# Connectors.net
KiCad netlist of a schematic drawn in Altium Designer
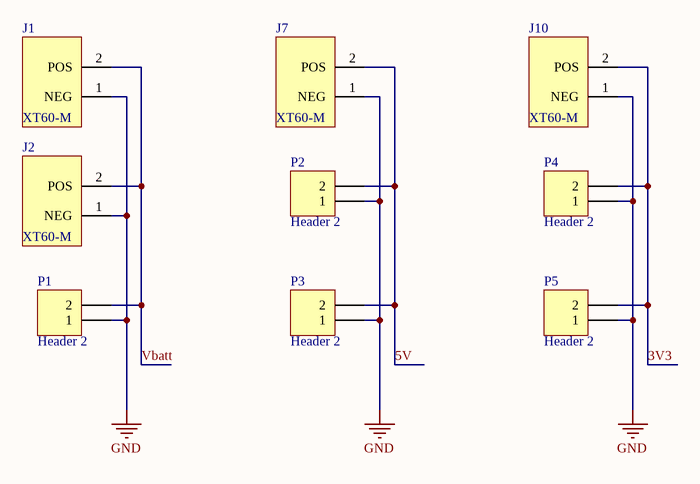
[diagram p0: Connectors.SchDoc]

(export (version "E")
  (design (tool "Eeschema 10.0.6"))
  (components
    (comp (ref "J1")
      (value "XT60-M")
      (footprint "*AMASS_XT60-M")
      (description "Plug; DC supply; XT60; male; PIN: 2; for cable; soldered; 30A; 500V")
      (fields (field (name "MF") "AMASS"))
      (libsource (lib "XT60-M") (part "XT60-M"))
    )
    (comp (ref "J2")
      (value "XT60-M")
      (footprint "*AMASS_XT60-M")
      (description "Plug; DC supply; XT60; male; PIN: 2; for cable; soldered; 30A; 500V")
      (fields (field (name "MF") "AMASS"))
      (libsource (lib "XT60-M") (part "XT60-M"))
    )
    (comp (ref "J7")
      (value "XT60-M")
      (footprint "*AMASS_XT60-M")
      (description "Plug; DC supply; XT60; male; PIN: 2; for cable; soldered; 30A; 500V")
      (fields (field (name "MF") "AMASS"))
      (libsource (lib "XT60-M") (part "XT60-M"))
    )
    (comp (ref "J10")
      (value "XT60-M")
      (footprint "*AMASS_XT60-M")
      (description "Plug; DC supply; XT60; male; PIN: 2; for cable; soldered; 30A; 500V")
      (fields (field (name "MF") "AMASS"))
      (libsource (lib "XT60-M") (part "XT60-M"))
    )
    (comp (ref "P1")
      (value "Header 2")
      (footprint "HDR1X2")
      (description "Header, 2-Pin")
      (fields (field (name "PUBLISHER") "Altium Limited"))
      (libsource (lib "Miscellaneous Connectors") (part "Header 2"))
    )
    (comp (ref "P2")
      (value "Header 2")
      (footprint "HDR1X2")
      (description "Header, 2-Pin")
      (fields (field (name "PUBLISHER") "Altium Limited"))
      (libsource (lib "Miscellaneous Connectors") (part "Header 2"))
    )
    (comp (ref "P3")
      (value "Header 2")
      (footprint "HDR1X2")
      (description "Header, 2-Pin")
      (fields (field (name "PUBLISHER") "Altium Limited"))
      (libsource (lib "Miscellaneous Connectors") (part "Header 2"))
    )
    (comp (ref "P4")
      (value "Header 2")
      (footprint "HDR1X2")
      (description "Header, 2-Pin")
      (fields (field (name "PUBLISHER") "Altium Limited"))
      (libsource (lib "Miscellaneous Connectors") (part "Header 2"))
    )
    (comp (ref "P5")
      (value "Header 2")
      (footprint "HDR1X2")
      (description "Header, 2-Pin")
      (fields (field (name "PUBLISHER") "Altium Limited"))
      (libsource (lib "Miscellaneous Connectors") (part "Header 2"))
    )
  )
  (nets
    (net (code "1") (name "/3V3") (class "Default")
      (node (ref "J10") (pin "2") (pinfunction "POS_2") (pintype "passive"))
      (node (ref "P4") (pin "2") (pinfunction "2_2") (pintype "passive"))
      (node (ref "P5") (pin "2") (pinfunction "2_2") (pintype "passive"))
    )
    (net (code "2") (name "/5V") (class "Default")
      (node (ref "J7") (pin "2") (pinfunction "POS_2") (pintype "passive"))
      (node (ref "P2") (pin "2") (pinfunction "2_2") (pintype "passive"))
      (node (ref "P3") (pin "2") (pinfunction "2_2") (pintype "passive"))
    )
    (net (code "3") (name "/Vbatt") (class "Default")
      (node (ref "J1") (pin "2") (pinfunction "POS_2") (pintype "passive"))
      (node (ref "J2") (pin "2") (pinfunction "POS_2") (pintype "passive"))
      (node (ref "P1") (pin "2") (pinfunction "2_2") (pintype "passive"))
    )
    (net (code "4") (name "GND") (class "Default")
      (node (ref "J1") (pin "1") (pinfunction "NEG_1") (pintype "passive"))
      (node (ref "J10") (pin "1") (pinfunction "NEG_1") (pintype "passive"))
      (node (ref "J2") (pin "1") (pinfunction "NEG_1") (pintype "passive"))
      (node (ref "J7") (pin "1") (pinfunction "NEG_1") (pintype "passive"))
      (node (ref "P1") (pin "1") (pinfunction "1_1") (pintype "passive"))
      (node (ref "P2") (pin "1") (pinfunction "1_1") (pintype "passive"))
      (node (ref "P3") (pin "1") (pinfunction "1_1") (pintype "passive"))
      (node (ref "P4") (pin "1") (pinfunction "1_1") (pintype "passive"))
      (node (ref "P5") (pin "1") (pinfunction "1_1") (pintype "passive"))
    )
  )
)
